# vreg.net
KiCad netlist of a schematic drawn in Altium Designer
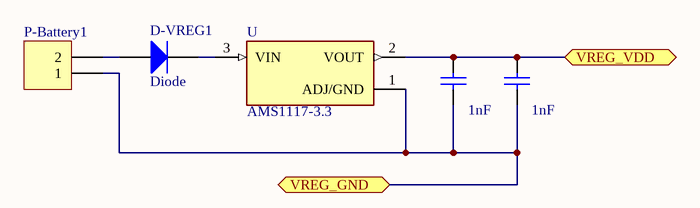
[diagram p0: vreg.SchDoc]

(export (version "E")
  (design (tool "Eeschema 10.0.6"))
  (components
    (comp (ref "C-VREG1")
      (value "1nF")
      (footprint "RAD-0.3")
      (description "Capacitor")
      (fields (field (name "Comment") "Cap") (field (name "PUBLISHER") "Altium Limited"))
      (libsource (lib "Miscellaneous Devices") (part "Cap"))
    )
    (comp (ref "C-VREG2")
      (value "1nF")
      (footprint "RAD-0.3")
      (description "Capacitor")
      (fields (field (name "Comment") "Cap") (field (name "PUBLISHER") "Altium Limited"))
      (libsource (lib "Miscellaneous Devices") (part "Cap"))
    )
    (comp (ref "D-VREG1")
      (value "Diode")
      (footprint "SMC")
      (description "Default Diode")
      (fields (field (name "PUBLISHER") "Altium Limited"))
      (libsource (lib "Miscellaneous Devices") (part "Diode"))
    )
    (comp (ref "P-Battery1")
      (value "Header 2")
      (footprint "HDR1X2")
      (description "Header, 2-Pin")
      (fields (field (name "PUBLISHER") "Altium Limited"))
      (libsource (lib "Miscellaneous Connectors") (part "Header 2"))
    )
    (comp (ref "U")
      (value "AMS1117-3.3")
      (footprint "SOT229P700X180-4N")
      (description "Sot223/Pkg 1-Amp 3.3-Volt Low Drop Out Voltage Regulatator")
      (fields (field (name "MF") "Advanced Monolithic Systems"))
      (libsource (lib "AMS1117-3.3") (part "AMS1117-3.3"))
    )
  )
  (nets
    (net (code "1") (name "/VREG_GND") (class "Default")
      (node (ref "C-VREG1") (pin "1") (pinfunction "1_1") (pintype "passive"))
      (node (ref "C-VREG2") (pin "1") (pinfunction "1_1") (pintype "passive"))
      (node (ref "P-Battery1") (pin "1") (pinfunction "1_1") (pintype "passive"))
      (node (ref "U") (pin "1") (pinfunction "ADJ/GND_1") (pintype "power_in"))
    )
    (net (code "2") (name "/VREG_VDD") (class "Default")
      (node (ref "C-VREG1") (pin "2") (pinfunction "2_2") (pintype "passive"))
      (node (ref "C-VREG2") (pin "2") (pinfunction "2_2") (pintype "passive"))
      (node (ref "U") (pin "2") (pinfunction "VOUT_2") (pintype "output"))
    )
    (net (code "3") (name "Net-(D-VREG1-A)") (class "Default")
      (node (ref "D-VREG1") (pin "1") (pinfunction "A_1") (pintype "passive"))
      (node (ref "P-Battery1") (pin "2") (pinfunction "2_2") (pintype "passive"))
    )
    (net (code "4") (name "Net-(D-VREG1-K)") (class "Default")
      (node (ref "D-VREG1") (pin "2") (pinfunction "K_2") (pintype "passive"))
      (node (ref "U") (pin "3") (pinfunction "VIN_3") (pintype "input"))
    )
  )
)
